# Grove_-_Recorder_v1_0.net
KiCad netlist of a schematic drawn in EAGLE
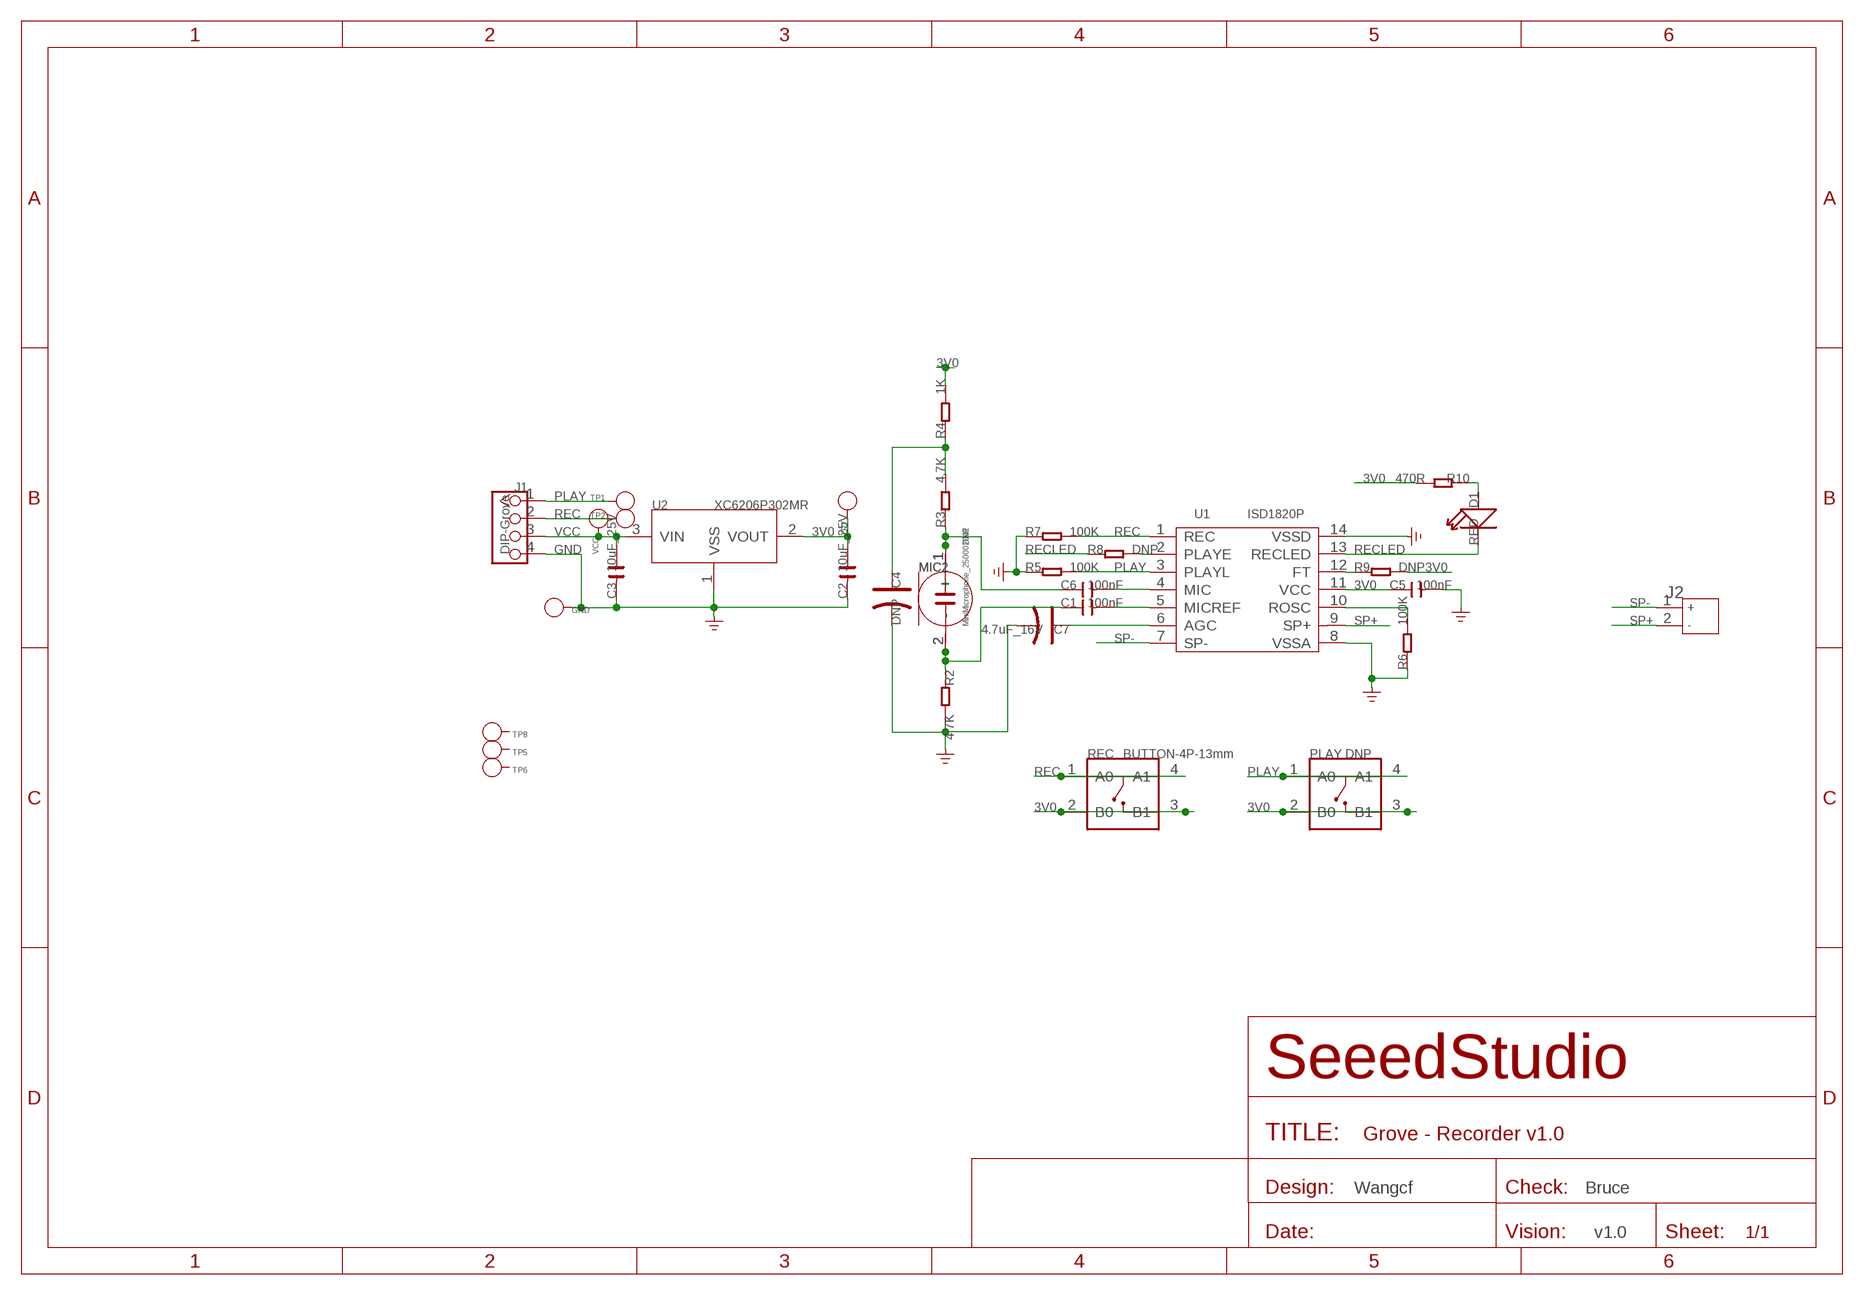
[diagram p0: schematic, sheet 1]

(export (version "E")
  (design (tool "Eeschema 10.0.6"))
  (components
    (comp (ref "C1")
      (value "100nF")
      (footprint "eagle-import:C0603")
      (libsource (lib "eagle-import") (part "C-0603"))
    )
    (comp (ref "C2")
      (value "10uF_25V")
      (footprint "eagle-import:C0805")
      (libsource (lib "eagle-import") (part "OPL_C-0805"))
    )
    (comp (ref "C3")
      (value "10uF_25V")
      (footprint "eagle-import:C0805")
      (libsource (lib "eagle-import") (part "OPL_C-0805"))
    )
    (comp (ref "C4")
      (value "DNP")
      (footprint "eagle-import:AVX-A")
      (libsource (lib "eagle-import") (part "CAP-AVX-A"))
    )
    (comp (ref "C5")
      (value "100nF")
      (footprint "eagle-import:C0603")
      (libsource (lib "eagle-import") (part "C-0603"))
    )
    (comp (ref "C6")
      (value "100nF")
      (footprint "eagle-import:C0603")
      (libsource (lib "eagle-import") (part "C-0603"))
    )
    (comp (ref "C7")
      (value "4.7uF_16V")
      (footprint "eagle-import:AVX-A")
      (libsource (lib "eagle-import") (part "C-POLAR-A"))
    )
    (comp (ref "D1")
      (value "RED")
      (footprint "eagle-import:LED-SIDE-VIEW-0603-RIGHT")
      (libsource (lib "eagle-import") (part "LED'RIGHT'"))
    )
    (comp (ref "GND")
      (value "PAD-TEST-POINT'4545'")
      (footprint "eagle-import:TP_4545")
      (fields (field (name "PARTNO") "DNP"))
      (libsource (lib "eagle-import") (part "PAD-TEST-POINT'4545'"))
    )
    (comp (ref "J1")
      (value "DIP-Grove")
      (footprint "eagle-import:4P-2.0")
      (libsource (lib "eagle-import") (part "TWIG-4P-2.0-2.0"))
    )
    (comp (ref "J2")
      (value "JACK-JST-2P-PW'2.0'")
      (footprint "eagle-import:JST-2.0")
      (libsource (lib "eagle-import") (part "JACK-JST-2P-PW'2.0'"))
    )
    (comp (ref "MIC1")
      (value "MiniMicrophone_250002001")
      (footprint "eagle-import:2P-D8.9MM")
      (libsource (lib "eagle-import") (part "MICROPHONE"))
    )
    (comp (ref "MIC2")
      (value "DNP")
      (footprint "eagle-import:2P-D8.9MM")
      (libsource (lib "eagle-import") (part "MICROPHONE"))
    )
    (comp (ref "PLAY")
      (value "DNP")
      (footprint "eagle-import:4P-6.0X6.0X5.0H")
      (libsource (lib "eagle-import") (part "BUTTON-4P-3110040P1"))
    )
    (comp (ref "R2")
      (value "4.7K")
      (footprint "eagle-import:R0603")
      (libsource (lib "eagle-import") (part "R-0603"))
    )
    (comp (ref "R3")
      (value "4.7K")
      (footprint "eagle-import:R0603")
      (libsource (lib "eagle-import") (part "R-0603"))
    )
    (comp (ref "R4")
      (value "1K")
      (footprint "eagle-import:R0603")
      (libsource (lib "eagle-import") (part "R-0603"))
    )
    (comp (ref "R5")
      (value "100K")
      (footprint "eagle-import:R0603")
      (libsource (lib "eagle-import") (part "R-0603"))
    )
    (comp (ref "R6")
      (value "100K")
      (footprint "eagle-import:R0603")
      (libsource (lib "eagle-import") (part "R-0603"))
    )
    (comp (ref "R7")
      (value "100K")
      (footprint "eagle-import:R0603")
      (libsource (lib "eagle-import") (part "R-0603"))
    )
    (comp (ref "R8")
      (value "DNP")
      (footprint "eagle-import:R0603")
      (libsource (lib "eagle-import") (part "R-0603"))
    )
    (comp (ref "R9")
      (value "DNP")
      (footprint "eagle-import:R0603")
      (libsource (lib "eagle-import") (part "R-0603"))
    )
    (comp (ref "R10")
      (value "470R")
      (footprint "eagle-import:R0603")
      (libsource (lib "eagle-import") (part "R-0603"))
    )
    (comp (ref "REC")
      (value "BUTTON-4P-13mm")
      (footprint "eagle-import:4P-6.0X6.0X5.0H")
      (libsource (lib "eagle-import") (part "BUTTON-4P-3110040P1"))
    )
    (comp (ref "TP1")
      (value "PAD-TEST-POINT'4545'")
      (footprint "eagle-import:TP_4545")
      (fields (field (name "PARTNO") "DNP"))
      (libsource (lib "eagle-import") (part "PAD-TEST-POINT'4545'"))
    )
    (comp (ref "TP2")
      (value "PAD-TEST-POINT'4545'")
      (footprint "eagle-import:TP_4545")
      (fields (field (name "PARTNO") "DNP"))
      (libsource (lib "eagle-import") (part "PAD-TEST-POINT'4545'"))
    )
    (comp (ref "TP5")
      (value "PAD-TEST-POINT'4545'")
      (footprint "eagle-import:TP_4545")
      (fields (field (name "PARTNO") "DNP"))
      (libsource (lib "eagle-import") (part "PAD-TEST-POINT'4545'"))
    )
    (comp (ref "TP6")
      (value "PAD-TEST-POINT'4545'")
      (footprint "eagle-import:TP_4545")
      (fields (field (name "PARTNO") "DNP"))
      (libsource (lib "eagle-import") (part "PAD-TEST-POINT'4545'"))
    )
    (comp (ref "TP7")
      (value "PAD-TEST-POINT'4545'")
      (footprint "eagle-import:TP_4545")
      (fields (field (name "PARTNO") "DNP"))
      (libsource (lib "eagle-import") (part "PAD-TEST-POINT'4545'"))
    )
    (comp (ref "TP8")
      (value "PAD-TEST-POINT'4545'")
      (footprint "eagle-import:TP_4545")
      (fields (field (name "PARTNO") "DNP"))
      (libsource (lib "eagle-import") (part "PAD-TEST-POINT'4545'"))
    )
    (comp (ref "U1")
      (value "ISD1820P")
      (footprint "eagle-import:DIP14")
      (libsource (lib "eagle-import") (part "ISD1820P"))
    )
    (comp (ref "U2")
      (value "XC6206P302MR")
      (footprint "eagle-import:SOT23")
      (libsource (lib "eagle-import") (part "XC6206MR"))
    )
    (comp (ref "VCC")
      (value "PAD-TEST-POINT'4545'")
      (footprint "eagle-import:TP_4545")
      (fields (field (name "PARTNO") "DNP"))
      (libsource (lib "eagle-import") (part "PAD-TEST-POINT'4545'"))
    )
  )
  (nets
    (net (code "1") (name "/3V0") (class "Default")
      (node (ref "C2") (pin "2") (pinfunction "2_2") (pintype "bidirectional"))
      (node (ref "C5") (pin "1") (pinfunction "1_1") (pintype "passive"))
      (node (ref "PLAY") (pin "2") (pinfunction "B0_2") (pintype "bidirectional"))
      (node (ref "PLAY") (pin "3") (pinfunction "B1_3") (pintype "bidirectional"))
      (node (ref "R10") (pin "2") (pinfunction "2_2") (pintype "passive"))
      (node (ref "R4") (pin "2") (pinfunction "2_2") (pintype "passive"))
      (node (ref "R9") (pin "2") (pinfunction "2_2") (pintype "passive"))
      (node (ref "REC") (pin "2") (pinfunction "B0_2") (pintype "bidirectional"))
      (node (ref "REC") (pin "3") (pinfunction "B1_3") (pintype "bidirectional"))
      (node (ref "TP7") (pin "T") (pinfunction "T_T") (pintype "bidirectional"))
      (node (ref "U1") (pin "11") (pinfunction "VCC_11") (pintype "bidirectional"))
      (node (ref "U2") (pin "2") (pinfunction "VOUT_2") (pintype "output"))
    )
    (net (code "2") (name "/PLAY") (class "Default")
      (node (ref "J1") (pin "1") (pinfunction "1_1") (pintype "bidirectional"))
      (node (ref "PLAY") (pin "1") (pinfunction "A0_1") (pintype "bidirectional"))
      (node (ref "PLAY") (pin "4") (pinfunction "A1_4") (pintype "bidirectional"))
      (node (ref "R5") (pin "2") (pinfunction "2_2") (pintype "passive"))
      (node (ref "TP1") (pin "T") (pinfunction "T_T") (pintype "bidirectional"))
      (node (ref "U1") (pin "3") (pinfunction "PLAYL_3") (pintype "bidirectional"))
    )
    (net (code "3") (name "/REC") (class "Default")
      (node (ref "J1") (pin "2") (pinfunction "2_2") (pintype "bidirectional"))
      (node (ref "R7") (pin "2") (pinfunction "2_2") (pintype "passive"))
      (node (ref "REC") (pin "1") (pinfunction "A0_1") (pintype "bidirectional"))
      (node (ref "REC") (pin "4") (pinfunction "A1_4") (pintype "bidirectional"))
      (node (ref "TP2") (pin "T") (pinfunction "T_T") (pintype "bidirectional"))
      (node (ref "U1") (pin "1") (pinfunction "REC_1") (pintype "bidirectional"))
    )
    (net (code "4") (name "/RECLED") (class "Default")
      (node (ref "D1") (pin "2") (pinfunction "-_2") (pintype "passive"))
      (node (ref "R8") (pin "1") (pinfunction "1_1") (pintype "passive"))
      (node (ref "U1") (pin "13") (pinfunction "RECLED_13") (pintype "bidirectional"))
    )
    (net (code "5") (name "/SP+") (class "Default")
      (node (ref "J2") (pin "2") (pinfunction "P$2_2") (pintype "bidirectional"))
      (node (ref "U1") (pin "9") (pinfunction "SP+_9") (pintype "bidirectional"))
    )
    (net (code "6") (name "/SP-") (class "Default")
      (node (ref "J2") (pin "1") (pinfunction "P$1_1") (pintype "bidirectional"))
      (node (ref "U1") (pin "7") (pinfunction "SP-_7") (pintype "bidirectional"))
    )
    (net (code "7") (name "/VCC") (class "Default")
      (node (ref "C3") (pin "2") (pinfunction "2_2") (pintype "bidirectional"))
      (node (ref "J1") (pin "3") (pinfunction "3_3") (pintype "bidirectional"))
      (node (ref "U2") (pin "3") (pinfunction "VIN_3") (pintype "input"))
      (node (ref "VCC") (pin "T") (pinfunction "T_T") (pintype "bidirectional"))
    )
    (net (code "8") (name "GND_POWER") (class "Default")
      (node (ref "C2") (pin "1") (pinfunction "1_1") (pintype "bidirectional"))
      (node (ref "C3") (pin "1") (pinfunction "1_1") (pintype "bidirectional"))
      (node (ref "C4") (pin "-") (pinfunction "-_-") (pintype "passive"))
      (node (ref "C5") (pin "2") (pinfunction "2_2") (pintype "passive"))
      (node (ref "C7") (pin "-") (pinfunction "2_-") (pintype "bidirectional"))
      (node (ref "GND") (pin "T") (pinfunction "T_T") (pintype "bidirectional"))
      (node (ref "J1") (pin "4") (pinfunction "4_4") (pintype "bidirectional"))
      (node (ref "R2") (pin "2") (pinfunction "2_2") (pintype "passive"))
      (node (ref "R5") (pin "1") (pinfunction "1_1") (pintype "passive"))
      (node (ref "R6") (pin "1") (pinfunction "1_1") (pintype "passive"))
      (node (ref "R7") (pin "1") (pinfunction "1_1") (pintype "passive"))
      (node (ref "U1") (pin "14") (pinfunction "VSSD_14") (pintype "bidirectional"))
      (node (ref "U1") (pin "8") (pinfunction "VSSA_8") (pintype "bidirectional"))
      (node (ref "U2") (pin "1") (pinfunction "VSS_1") (pintype "power_in"))
    )
    (net (code "9") (name "Net-(C4-Pad+)") (class "Default")
      (node (ref "C4") (pin "+") (pinfunction "+_+") (pintype "passive"))
      (node (ref "R3") (pin "2") (pinfunction "2_2") (pintype "passive"))
      (node (ref "R4") (pin "1") (pinfunction "1_1") (pintype "passive"))
    )
    (net (code "10") (name "Net-(C7-1)") (class "Default")
      (node (ref "C7") (pin "+") (pinfunction "1_+") (pintype "bidirectional"))
      (node (ref "U1") (pin "6") (pinfunction "AGC_6") (pintype "bidirectional"))
    )
    (net (code "11") (name "Net-(D1-+)") (class "Default")
      (node (ref "D1") (pin "1") (pinfunction "+_1") (pintype "passive"))
      (node (ref "R10") (pin "1") (pinfunction "1_1") (pintype "passive"))
    )
    (net (code "12") (name "Net-(MIC1-+)") (class "Default")
      (node (ref "C6") (pin "1") (pinfunction "1_1") (pintype "passive"))
      (node (ref "MIC1") (pin "1") (pinfunction "+_1") (pintype "bidirectional"))
      (node (ref "MIC2") (pin "1") (pinfunction "+_1") (pintype "bidirectional"))
      (node (ref "R3") (pin "1") (pinfunction "1_1") (pintype "passive"))
    )
    (net (code "13") (name "Net-(MIC1--)") (class "Default")
      (node (ref "C1") (pin "1") (pinfunction "1_1") (pintype "passive"))
      (node (ref "MIC1") (pin "2") (pinfunction "-_2") (pintype "bidirectional"))
      (node (ref "MIC2") (pin "2") (pinfunction "-_2") (pintype "bidirectional"))
      (node (ref "R2") (pin "1") (pinfunction "1_1") (pintype "passive"))
    )
    (net (code "14") (name "Net-(U1-FT)") (class "Default")
      (node (ref "R9") (pin "1") (pinfunction "1_1") (pintype "passive"))
      (node (ref "U1") (pin "12") (pinfunction "FT_12") (pintype "bidirectional"))
    )
    (net (code "15") (name "Net-(U1-MIC)") (class "Default")
      (node (ref "C6") (pin "2") (pinfunction "2_2") (pintype "passive"))
      (node (ref "U1") (pin "4") (pinfunction "MIC_4") (pintype "bidirectional"))
    )
    (net (code "16") (name "Net-(U1-MICREF)") (class "Default")
      (node (ref "C1") (pin "2") (pinfunction "2_2") (pintype "passive"))
      (node (ref "U1") (pin "5") (pinfunction "MICREF_5") (pintype "bidirectional"))
    )
    (net (code "17") (name "Net-(U1-PLAYE)") (class "Default")
      (node (ref "R8") (pin "2") (pinfunction "2_2") (pintype "passive"))
      (node (ref "U1") (pin "2") (pinfunction "PLAYE_2") (pintype "bidirectional"))
    )
    (net (code "18") (name "Net-(U1-ROSC)") (class "Default")
      (node (ref "R6") (pin "2") (pinfunction "2_2") (pintype "passive"))
      (node (ref "U1") (pin "10") (pinfunction "ROSC_10") (pintype "bidirectional"))
    )
    (net (code "19") (name "unconnected-(TP5-PadT)") (class "Default")
      (node (ref "TP5") (pin "T") (pinfunction "T_T") (pintype "bidirectional"))
    )
    (net (code "20") (name "unconnected-(TP6-PadT)") (class "Default")
      (node (ref "TP6") (pin "T") (pinfunction "T_T") (pintype "bidirectional"))
    )
    (net (code "21") (name "unconnected-(TP8-PadT)") (class "Default")
      (node (ref "TP8") (pin "T") (pinfunction "T_T") (pintype "bidirectional"))
    )
  )
)
